# ProDoc_hub_SL2_1A.net
KiCad netlist of a schematic drawn in EasyEDA Pro
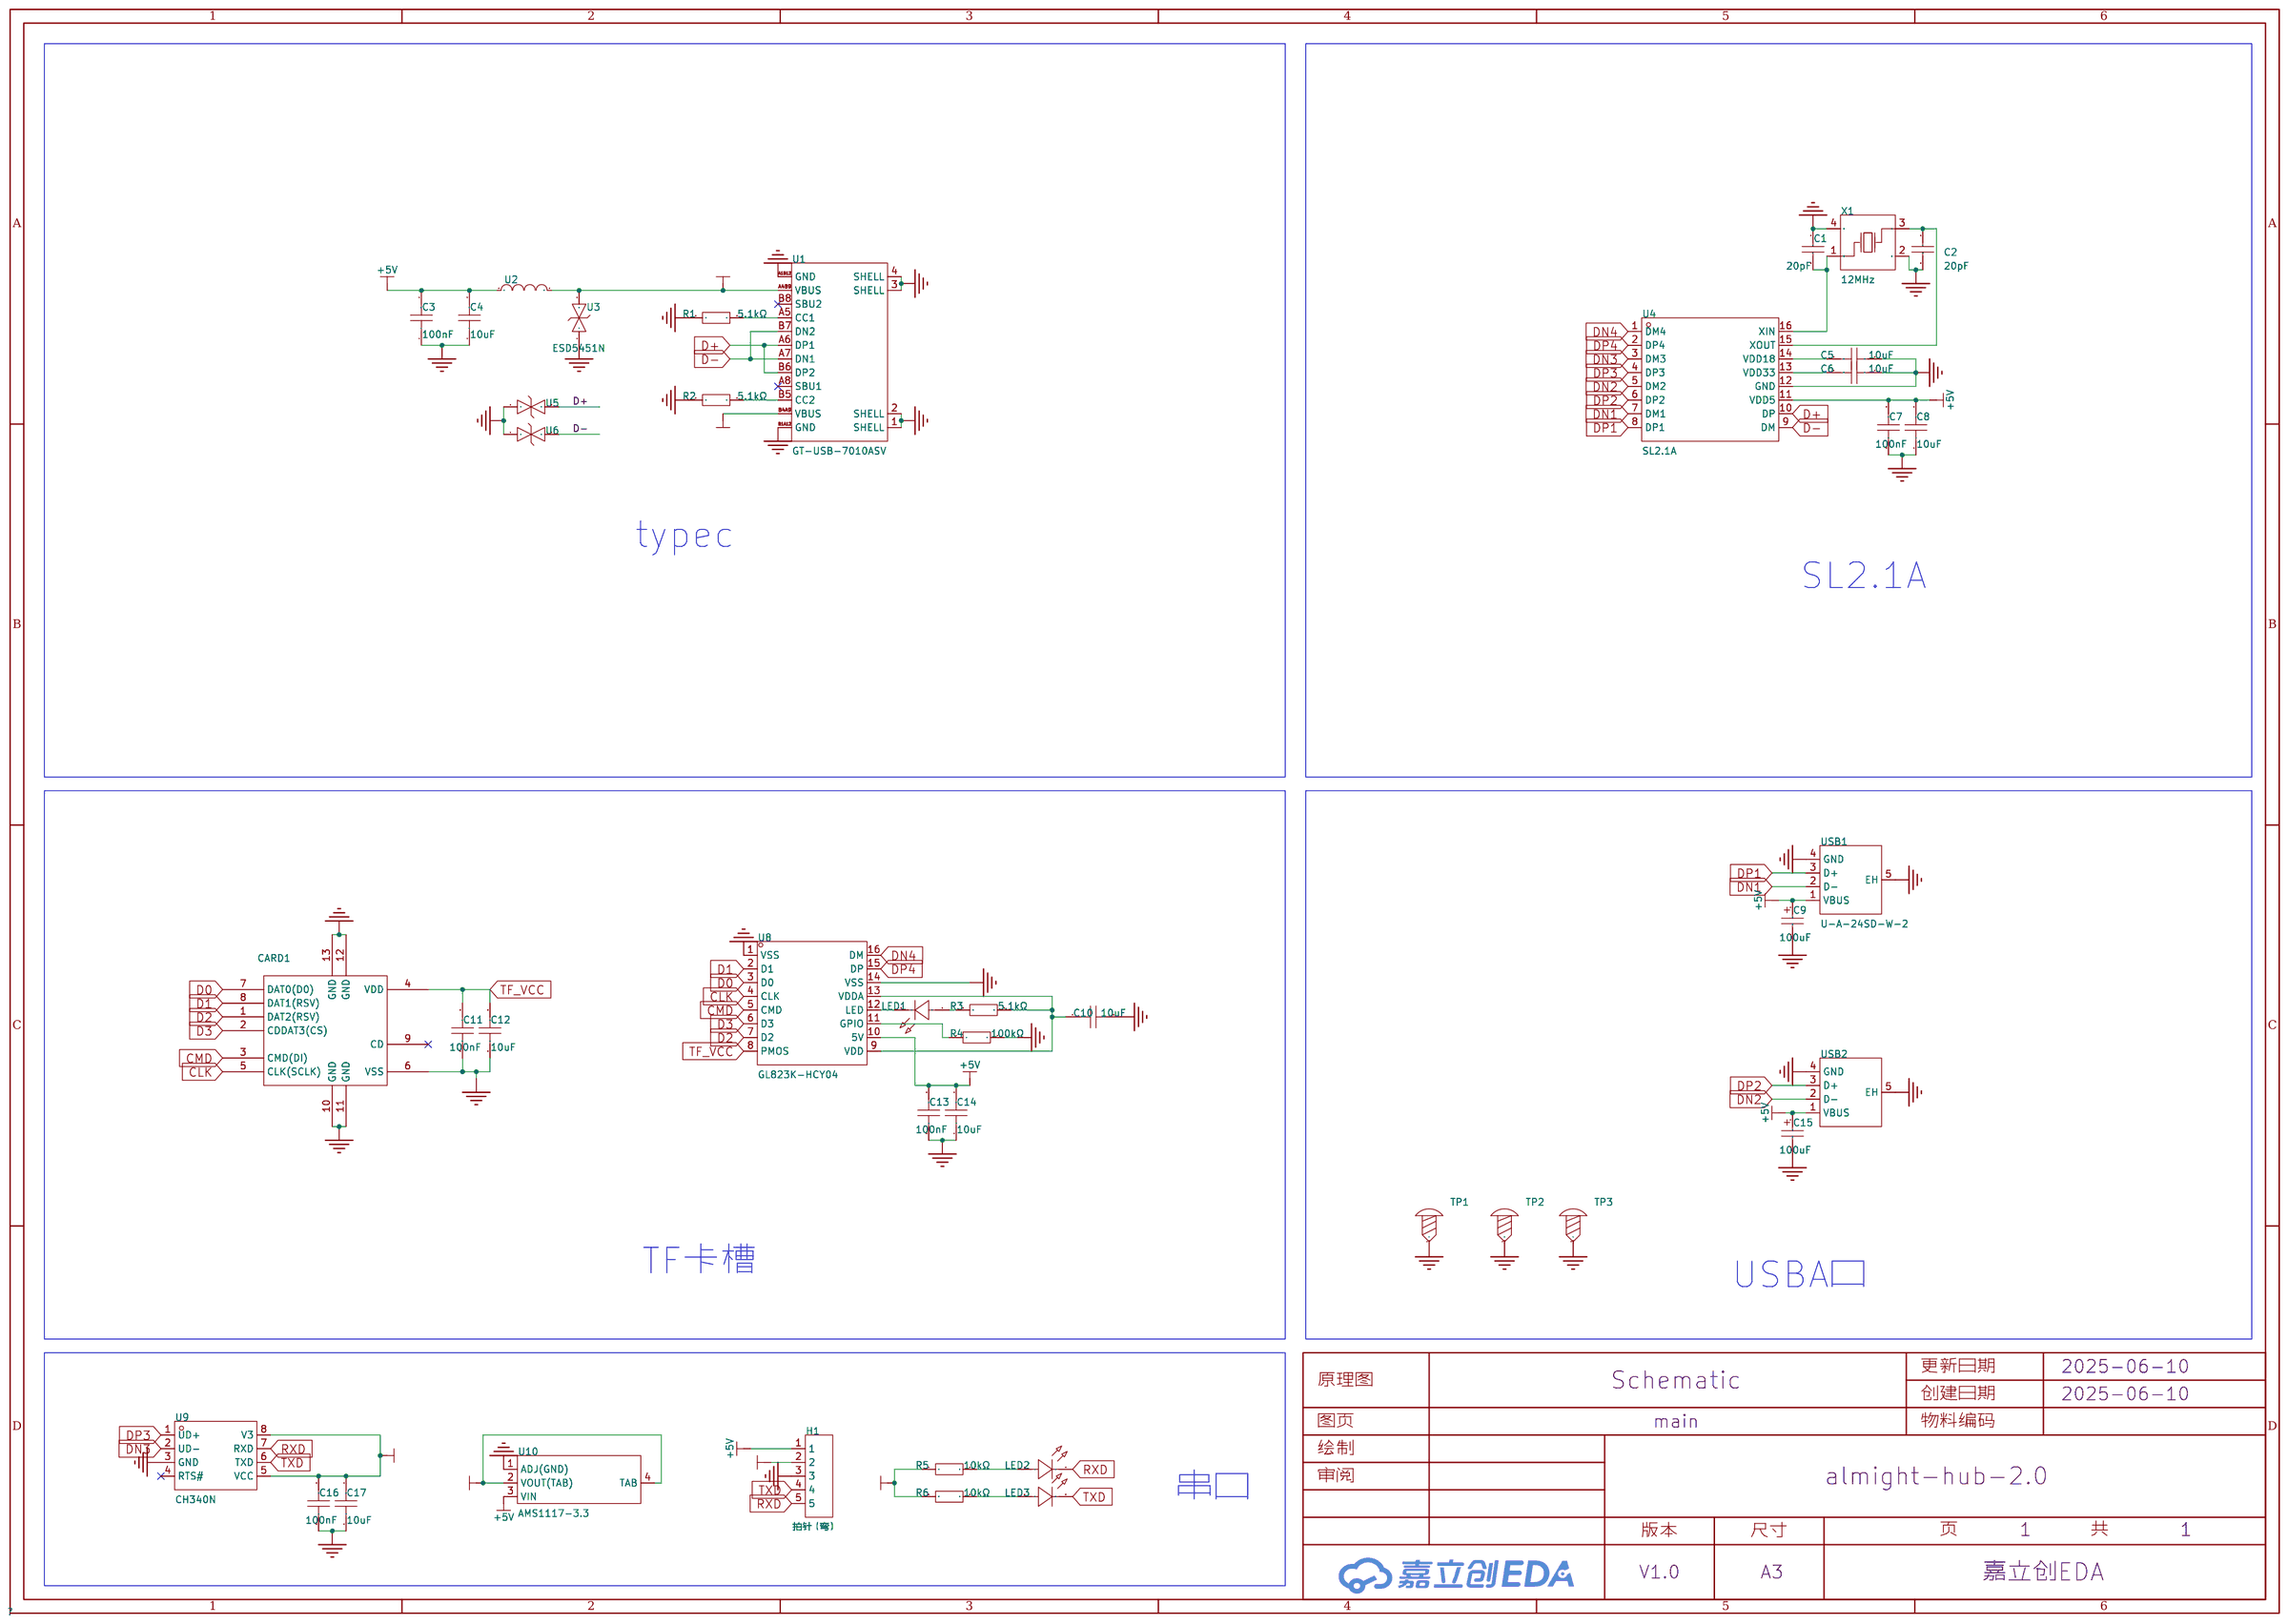
[diagram p0: schematic sheet]

(export (version "E")
  (design (tool "Eeschema 10.0.6"))
  (components
    (comp (ref "C1")
      (value "20pF")
      (footprint "easyedapro:C0402")
      (description "容值:20pF;精度:±5%;额定电压:50V;材质(温度系数):C0G;")
      (fields (field (name "Manufacturer Part") "0402CG200J500NT") (field (name "Manufacturer") "FH(风华)"))
      (libsource (lib "easyedapro") (part "0402CG200J500NT"))
    )
    (comp (ref "C2")
      (value "20pF")
      (footprint "easyedapro:C0402")
      (description "容值:20pF;精度:±5%;额定电压:50V;材质(温度系数):C0G;")
      (fields (field (name "Manufacturer Part") "0402CG200J500NT") (field (name "Manufacturer") "FH(风华)"))
      (libsource (lib "easyedapro") (part "0402CG200J500NT"))
    )
    (comp (ref "C3")
      (value "100nF")
      (footprint "easyedapro:C0402")
      (description "容值:10uF;精度:±20%;额定电压:10V;材质(温度系数):X5R;")
      (fields
        (field (name "Manufacturer Part") "HGC0402R5106M100NTEJ")
        (field (name "Manufacturer") "Chinocera(华瓷)")
      )
      (libsource (lib "easyedapro") (part "HGC0402R5106M100NTEJ"))
    )
    (comp (ref "C4")
      (value "10uF")
      (footprint "easyedapro:C0402")
      (description "容值:10uF;精度:±20%;额定电压:10V;材质(温度系数):X5R;")
      (fields
        (field (name "Manufacturer Part") "HGC0402R5106M100NTEJ")
        (field (name "Manufacturer") "Chinocera(华瓷)")
      )
      (libsource (lib "easyedapro") (part "HGC0402R5106M100NTEJ"))
    )
    (comp (ref "C5")
      (value "10uF")
      (footprint "easyedapro:C0402")
      (description "容值:10uF;精度:±20%;额定电压:10V;材质(温度系数):X5R;")
      (fields
        (field (name "Manufacturer Part") "HGC0402R5106M100NTEJ")
        (field (name "Manufacturer") "Chinocera(华瓷)")
      )
      (libsource (lib "easyedapro") (part "HGC0402R5106M100NTEJ"))
    )
    (comp (ref "C6")
      (value "10uF")
      (footprint "easyedapro:C0402")
      (description "容值:10uF;精度:±20%;额定电压:10V;材质(温度系数):X5R;")
      (fields
        (field (name "Manufacturer Part") "HGC0402R5106M100NTEJ")
        (field (name "Manufacturer") "Chinocera(华瓷)")
      )
      (libsource (lib "easyedapro") (part "HGC0402R5106M100NTEJ"))
    )
    (comp (ref "C7")
      (value "100nF")
      (footprint "easyedapro:C0402")
      (description "容值:10uF;精度:±20%;额定电压:10V;材质(温度系数):X5R;")
      (fields
        (field (name "Manufacturer Part") "HGC0402R5106M100NTEJ")
        (field (name "Manufacturer") "Chinocera(华瓷)")
      )
      (libsource (lib "easyedapro") (part "HGC0402R5106M100NTEJ"))
    )
    (comp (ref "C8")
      (value "10uF")
      (footprint "easyedapro:C0402")
      (description "容值:10uF;精度:±20%;额定电压:10V;材质(温度系数):X5R;")
      (fields
        (field (name "Manufacturer Part") "HGC0402R5106M100NTEJ")
        (field (name "Manufacturer") "Chinocera(华瓷)")
      )
      (libsource (lib "easyedapro") (part "HGC0402R5106M100NTEJ"))
    )
    (comp (ref "C9")
      (value "100uF")
      (footprint "easyedapro:CASE-B_3528")
      (description "容值:100uF;精度:±10%;额定电压:6.3V;等效串联电阻(ESR):1.7Ω@100kHz;")
      (fields (field (name "Manufacturer Part") "TAJB107K006RNJ") (field (name "Manufacturer") "Kyocera AVX"))
      (libsource (lib "easyedapro") (part "TAJB107K006RNJ"))
    )
    (comp (ref "C10")
      (value "10uF")
      (footprint "easyedapro:C0402")
      (description "容值:10uF;精度:±20%;额定电压:10V;材质(温度系数):X5R;")
      (fields
        (field (name "Manufacturer Part") "HGC0402R5106M100NTEJ")
        (field (name "Manufacturer") "Chinocera(华瓷)")
      )
      (libsource (lib "easyedapro") (part "HGC0402R5106M100NTEJ"))
    )
    (comp (ref "C11")
      (value "100nF")
      (footprint "easyedapro:C0402")
      (description "容值:10uF;精度:±20%;额定电压:10V;材质(温度系数):X5R;")
      (fields
        (field (name "Manufacturer Part") "HGC0402R5106M100NTEJ")
        (field (name "Manufacturer") "Chinocera(华瓷)")
      )
      (libsource (lib "easyedapro") (part "HGC0402R5106M100NTEJ"))
    )
    (comp (ref "C12")
      (value "10uF")
      (footprint "easyedapro:C0402")
      (description "容值:10uF;精度:±20%;额定电压:10V;材质(温度系数):X5R;")
      (fields
        (field (name "Manufacturer Part") "HGC0402R5106M100NTEJ")
        (field (name "Manufacturer") "Chinocera(华瓷)")
      )
      (libsource (lib "easyedapro") (part "HGC0402R5106M100NTEJ"))
    )
    (comp (ref "C13")
      (value "100nF")
      (footprint "easyedapro:C0402")
      (description "容值:10uF;精度:±20%;额定电压:10V;材质(温度系数):X5R;")
      (fields
        (field (name "Manufacturer Part") "HGC0402R5106M100NTEJ")
        (field (name "Manufacturer") "Chinocera(华瓷)")
      )
      (libsource (lib "easyedapro") (part "HGC0402R5106M100NTEJ"))
    )
    (comp (ref "C14")
      (value "10uF")
      (footprint "easyedapro:C0402")
      (description "容值:10uF;精度:±20%;额定电压:10V;材质(温度系数):X5R;")
      (fields
        (field (name "Manufacturer Part") "HGC0402R5106M100NTEJ")
        (field (name "Manufacturer") "Chinocera(华瓷)")
      )
      (libsource (lib "easyedapro") (part "HGC0402R5106M100NTEJ"))
    )
    (comp (ref "C15")
      (value "100uF")
      (footprint "easyedapro:CASE-B_3528")
      (description "容值:100uF;精度:±10%;额定电压:6.3V;等效串联电阻(ESR):1.7Ω@100kHz;")
      (fields (field (name "Manufacturer Part") "TAJB107K006RNJ") (field (name "Manufacturer") "Kyocera AVX"))
      (libsource (lib "easyedapro") (part "TAJB107K006RNJ"))
    )
    (comp (ref "C16")
      (value "100nF")
      (footprint "easyedapro:C0402")
      (description "容值:10uF;精度:±20%;额定电压:10V;材质(温度系数):X5R;")
      (fields
        (field (name "Manufacturer Part") "HGC0402R5106M100NTEJ")
        (field (name "Manufacturer") "Chinocera(华瓷)")
      )
      (libsource (lib "easyedapro") (part "HGC0402R5106M100NTEJ"))
    )
    (comp (ref "C17")
      (value "10uF")
      (footprint "easyedapro:C0402")
      (description "容值:10uF;精度:±20%;额定电压:10V;材质(温度系数):X5R;")
      (fields
        (field (name "Manufacturer Part") "HGC0402R5106M100NTEJ")
        (field (name "Manufacturer") "Chinocera(华瓷)")
      )
      (libsource (lib "easyedapro") (part "HGC0402R5106M100NTEJ"))
    )
    (comp (ref "CARD1")
      (value "TF-01A")
      (footprint "easyedapro:TF-SMD_TF-01A")
      (description "卡连接方式:自弹式;卡类型:MicroSD卡(TF卡);连接器类型:卡座;本体最大高度:1.85mm;工作温度范围:-;")
      (fields (field (name "Manufacturer") "韩国韩荣"))
      (libsource (lib "easyedapro") (part "TF-01A"))
    )
    (comp (ref "H1")
      (value "拍针（弯）")
      (footprint "easyedapro:HDR-TH_5P-P2.54-H-M-W10.4")
      (fields (field (name "Manufacturer") "XFCN(兴飞)"))
      (libsource (lib "easyedapro") (part "PZ254R-11-05P"))
    )
    (comp (ref "LED1")
      (value "A-SP192DGHC-C01-4T")
      (footprint "easyedapro:LED0603-FD")
      (fields (field (name "Manufacturer") "Amicc(欧密格光电)"))
      (libsource (lib "easyedapro") (part "A-SP192DGHC-C01-4T"))
    )
    (comp (ref "LED2")
      (value "A-SP192DGHC-C01-4T")
      (footprint "easyedapro:LED0603-FD")
      (fields (field (name "Manufacturer") "Amicc(欧密格光电)"))
      (libsource (lib "easyedapro") (part "A-SP192DGHC-C01-4T"))
    )
    (comp (ref "LED3")
      (value "A-SP192DGHC-C01-4T")
      (footprint "easyedapro:LED0603-FD")
      (fields (field (name "Manufacturer") "Amicc(欧密格光电)"))
      (libsource (lib "easyedapro") (part "A-SP192DGHC-C01-4T"))
    )
    (comp (ref "R1")
      (value "5.1kΩ")
      (footprint "easyedapro:R0402")
      (description "电阻类型:厚膜电阻;阻值:5.1kΩ;精度:±1%;功率:62.5mW;工作电压:50V;温度系数:±100ppm/°C;")
      (fields (field (name "Manufacturer Part") "RC0402FR-075K1L") (field (name "Manufacturer") "YAGEO(国巨)"))
      (libsource (lib "easyedapro") (part "RC0402FR-075K1L"))
    )
    (comp (ref "R2")
      (value "5.1kΩ")
      (footprint "easyedapro:R0402")
      (description "电阻类型:厚膜电阻;阻值:5.1kΩ;精度:±1%;功率:62.5mW;工作电压:50V;温度系数:±100ppm/°C;")
      (fields (field (name "Manufacturer Part") "RC0402FR-075K1L") (field (name "Manufacturer") "YAGEO(国巨)"))
      (libsource (lib "easyedapro") (part "RC0402FR-075K1L"))
    )
    (comp (ref "R3")
      (value "5.1kΩ")
      (footprint "easyedapro:R0402")
      (description "电阻类型:厚膜电阻;阻值:5.1kΩ;精度:±1%;功率:62.5mW;工作电压:50V;温度系数:±100ppm/°C;")
      (fields (field (name "Manufacturer Part") "RC0402FR-075K1L") (field (name "Manufacturer") "YAGEO(国巨)"))
      (libsource (lib "easyedapro") (part "RC0402FR-075K1L"))
    )
    (comp (ref "R4")
      (value "100kΩ")
      (footprint "easyedapro:R0402")
      (description "电阻类型:厚膜电阻;阻值:5.1kΩ;精度:±1%;功率:62.5mW;工作电压:50V;温度系数:±100ppm/°C;")
      (fields (field (name "Manufacturer Part") "RC0402FR-075K1L") (field (name "Manufacturer") "YAGEO(国巨)"))
      (libsource (lib "easyedapro") (part "RC0402FR-075K1L"))
    )
    (comp (ref "R5")
      (value "10kΩ")
      (footprint "easyedapro:R0402")
      (description "电阻类型:厚膜电阻;阻值:5.1kΩ;精度:±1%;功率:62.5mW;工作电压:50V;温度系数:±100ppm/°C;")
      (fields (field (name "Manufacturer Part") "RC0402FR-075K1L") (field (name "Manufacturer") "YAGEO(国巨)"))
      (libsource (lib "easyedapro") (part "RC0402FR-075K1L"))
    )
    (comp (ref "R6")
      (value "10kΩ")
      (footprint "easyedapro:R0402")
      (description "电阻类型:厚膜电阻;阻值:5.1kΩ;精度:±1%;功率:62.5mW;工作电压:50V;温度系数:±100ppm/°C;")
      (fields (field (name "Manufacturer Part") "RC0402FR-075K1L") (field (name "Manufacturer") "YAGEO(国巨)"))
      (libsource (lib "easyedapro") (part "RC0402FR-075K1L"))
    )
    (comp (ref "TP1") (value "~") (footprint "easyedapro:M1螺丝孔") (libsource (lib "easyedapro") (part "螺丝孔")))
    (comp (ref "TP2") (value "~") (footprint "easyedapro:M1螺丝孔") (libsource (lib "easyedapro") (part "螺丝孔")))
    (comp (ref "TP3") (value "~") (footprint "easyedapro:M1螺丝孔") (libsource (lib "easyedapro") (part "螺丝孔")))
    (comp (ref "U1")
      (value "GT-USB-7010ASV")
      (footprint "easyedapro:USB-C-SMD_G-SWITCH_GT-USB-7010ASV")
      (description "连接器类型:Type-C;标准:USB 2.0;公母:母;安装方式:卧贴;触点数量:16P;端口数量:1;额定电流 - 电源:3A;工作温度范围:-40°C~+85°C;")
      (fields (field (name "Manufacturer") "G-Switch(品赞)"))
      (libsource (lib "easyedapro") (part "GT-USB-7010ASV"))
    )
    (comp (ref "U2")
      (value "UPZ1608U221-2R2TF")
      (footprint "easyedapro:L0603")
      (description "标称阻抗@测试频率:220Ω@100MHz;误差:±25%;直流电阻(RDC):50mΩ;")
      (fields (field (name "Manufacturer") "Sunlord(顺络)"))
      (libsource (lib "easyedapro") (part "UPZ1608U221-2R2TF"))
    )
    (comp (ref "U3")
      (value "ESD5451N")
      (footprint "easyedapro:DFN1006-2L-BI")
      (description "极性:双向;反向截止电压(Vrwm):5V;最大钳位电压:9.8V;峰值脉冲电流(Ipp):9A;击穿电压:8V;")
      (fields (field (name "Manufacturer") "HXY MOSFET(华轩阳电子)"))
      (libsource (lib "easyedapro") (part "ESD5451N_C5261080"))
    )
    (comp (ref "U4")
      (value "SL2.1A")
      (footprint "easyedapro:SOP-16_L10.0-W3.9-P1.27-LS6.0-BL")
      (description "SL2.1A是一颗高集成度,高性能,低功耗的USB2.0集线器主控芯片，支持USB2.0高速(480MHz),全速(12MHz)和低速模式(1.5MHz)，内置12MHz晶体振荡器。")
      (fields (field (name "Manufacturer") "CoreChips(和芯润德)"))
      (libsource (lib "easyedapro") (part "SL2.1A"))
    )
    (comp (ref "U5")
      (value "ESD5451N")
      (footprint "easyedapro:DFN1006-2L-BI")
      (description "极性:双向;反向截止电压(Vrwm):5V;最大钳位电压:9.8V;峰值脉冲电流(Ipp):9A;击穿电压:8V;")
      (fields (field (name "Manufacturer") "HXY MOSFET(华轩阳电子)"))
      (libsource (lib "easyedapro") (part "ESD5451N_C5261080"))
    )
    (comp (ref "U6")
      (value "ESD5451N")
      (footprint "easyedapro:DFN1006-2L-BI")
      (description "极性:双向;反向截止电压(Vrwm):5V;最大钳位电压:9.8V;峰值脉冲电流(Ipp):9A;击穿电压:8V;")
      (fields (field (name "Manufacturer") "HXY MOSFET(华轩阳电子)"))
      (libsource (lib "easyedapro") (part "ESD5451N_C5261080"))
    )
    (comp (ref "U8")
      (value "GL823K-HCY04")
      (footprint "easyedapro:SSOP-16_L4.9-W3.9-P0.64-LS6.0-BL")
      (description "应用功能:-;接口协议:-;")
      (fields (field (name "Manufacturer") "GENESYS(创惟)"))
      (libsource (lib "easyedapro") (part "GL823K-HCY04"))
    )
    (comp (ref "U9")
      (value "CH340N")
      (footprint "easyedapro:SOP-8_L5.0-W4.0-P1.27-LS6.0-BL")
      (description "应用功能:USB转串口;接口协议:USB 2.0;通道数:-;数据速率:2Mbps;")
      (fields (field (name "Manufacturer") "WCH(南京沁恒)"))
      (libsource (lib "easyedapro") (part "CH340N"))
    )
    (comp (ref "U10")
      (value "AMS1117-3.3")
      (footprint "easyedapro:SOT-223-4_L6.5-W3.5-P2.30-LS7.0-BR")
      (description "输出类型:固定;工作电压:12V;输出电压:3.3V;输出电流:1A;电源纹波抑制比(PSRR):60dB@(120Hz);输出极性:正极;")
      (fields (field (name "Manufacturer") "UMW(友台半导体)"))
      (libsource (lib "easyedapro") (part "AMS1117-3.3_C347222"))
    )
    (comp (ref "USB1")
      (value "U-A-24SD-W-2")
      (footprint "easyedapro:USB-A-SMD_U-A-24SD-W-2")
      (description "连接器类型:Type-A;标准:USB 2.0;公母:母;端口数量:1;触点数量:4P;安装方式:沉板;额定电流 - 电源:1.5A;工作温度范围:-;")
      (fields (field (name "Manufacturer") "韩国韩荣"))
      (libsource (lib "easyedapro") (part "U-A-24SD-W-2"))
    )
    (comp (ref "USB2")
      (value "U-A-24SD-W-2")
      (footprint "easyedapro:USB-A-SMD_U-A-24SD-W-2")
      (description "连接器类型:Type-A;标准:USB 2.0;公母:母;端口数量:1;触点数量:4P;安装方式:沉板;额定电流 - 电源:1.5A;工作温度范围:-;")
      (fields (field (name "Manufacturer") "韩国韩荣"))
      (libsource (lib "easyedapro") (part "U-A-24SD-W-2"))
    )
    (comp (ref "X1")
      (value "12MHz")
      (footprint "easyedapro:CRYSTAL-SMD_4P-L3.2-W2.5-BL")
      (description "晶振类型:贴片晶振;频率:12MHz;常温频差:±10ppm;外接负载电容:20pF;频率稳定度(全温):±20ppm;")
      (fields (field (name "Manufacturer Part") "X322512MSB4SI") (field (name "Manufacturer") "YXC(扬兴晶振)"))
      (libsource (lib "easyedapro") (part "X322512MSB4SI"))
    )
  )
  (nets
    (net (code "1") (name "+5V") (class "Default")
      (node (ref "C13") (pin "2") (pinfunction "2_2") (pintype "unspecified"))
      (node (ref "C14") (pin "2") (pinfunction "2_2") (pintype "unspecified"))
      (node (ref "C15") (pin "1") (pinfunction "1_1") (pintype "input"))
      (node (ref "C3") (pin "2") (pinfunction "2_2") (pintype "unspecified"))
      (node (ref "C4") (pin "2") (pinfunction "2_2") (pintype "unspecified"))
      (node (ref "C7") (pin "2") (pinfunction "2_2") (pintype "unspecified"))
      (node (ref "C8") (pin "2") (pinfunction "2_2") (pintype "unspecified"))
      (node (ref "C9") (pin "1") (pinfunction "1_1") (pintype "input"))
      (node (ref "H1") (pin "1") (pinfunction "1_1") (pintype "unspecified"))
      (node (ref "U10") (pin "3") (pinfunction "VIN_3") (pintype "unspecified"))
      (node (ref "U2") (pin "1") (pinfunction "1_1") (pintype "unspecified"))
      (node (ref "U4") (pin "11") (pinfunction "VDD5_11") (pintype "unspecified"))
      (node (ref "U8") (pin "10") (pinfunction "5V_10") (pintype "unspecified"))
      (node (ref "USB1") (pin "1") (pinfunction "VBUS_1") (pintype "unspecified"))
      (node (ref "USB2") (pin "1") (pinfunction "VBUS_1") (pintype "unspecified"))
    )
    (net (code "2") (name "3V3") (class "Default")
      (node (ref "C16") (pin "2") (pinfunction "2_2") (pintype "unspecified"))
      (node (ref "C17") (pin "2") (pinfunction "2_2") (pintype "unspecified"))
      (node (ref "H1") (pin "2") (pinfunction "2_2") (pintype "unspecified"))
      (node (ref "R5") (pin "1") (pinfunction "1_1") (pintype "input"))
      (node (ref "R6") (pin "1") (pinfunction "1_1") (pintype "input"))
      (node (ref "U10") (pin "2") (pinfunction "VOUT(TAB)_2") (pintype "unspecified"))
      (node (ref "U10") (pin "4") (pinfunction "TAB_4") (pintype "unspecified"))
      (node (ref "U9") (pin "5") (pinfunction "VCC_5") (pintype "unspecified"))
      (node (ref "U9") (pin "8") (pinfunction "V3_8") (pintype "unspecified"))
    )
    (net (code "3") (name "CLK") (class "Default")
      (node (ref "CARD1") (pin "5") (pinfunction "CLK(SCLK)_5") (pintype "input"))
      (node (ref "U8") (pin "4") (pinfunction "CLK_4") (pintype "unspecified"))
    )
    (net (code "4") (name "CMD") (class "Default")
      (node (ref "CARD1") (pin "3") (pinfunction "CMD(DI)_3") (pintype "input"))
      (node (ref "U8") (pin "5") (pinfunction "CMD_5") (pintype "unspecified"))
    )
    (net (code "5") (name "D+") (class "Default")
      (node (ref "U1") (pin "A6") (pinfunction "DP1_A6") (pintype "unspecified"))
      (node (ref "U1") (pin "B6") (pinfunction "DP2_B6") (pintype "unspecified"))
      (node (ref "U4") (pin "10") (pinfunction "DP_10") (pintype "unspecified"))
      (node (ref "U5") (pin "2") (pinfunction "2_2") (pintype "unspecified"))
    )
    (net (code "6") (name "D-") (class "Default")
      (node (ref "U1") (pin "A7") (pinfunction "DN1_A7") (pintype "unspecified"))
      (node (ref "U1") (pin "B7") (pinfunction "DN2_B7") (pintype "unspecified"))
      (node (ref "U4") (pin "9") (pinfunction "DM_9") (pintype "unspecified"))
      (node (ref "U6") (pin "2") (pinfunction "2_2") (pintype "unspecified"))
    )
    (net (code "7") (name "D0") (class "Default")
      (node (ref "CARD1") (pin "7") (pinfunction "DAT0(D0)_7") (pintype "bidirectional"))
      (node (ref "U8") (pin "3") (pinfunction "D0_3") (pintype "unspecified"))
    )
    (net (code "8") (name "D1") (class "Default")
      (node (ref "CARD1") (pin "8") (pinfunction "DAT1(RSV)_8") (pintype "bidirectional"))
      (node (ref "U8") (pin "2") (pinfunction "D1_2") (pintype "unspecified"))
    )
    (net (code "9") (name "D2") (class "Default")
      (node (ref "CARD1") (pin "1") (pinfunction "DAT2(RSV)_1") (pintype "bidirectional"))
      (node (ref "U8") (pin "7") (pinfunction "D2_7") (pintype "unspecified"))
    )
    (net (code "10") (name "D3") (class "Default")
      (node (ref "CARD1") (pin "2") (pinfunction "CDDAT3(CS)_2") (pintype "bidirectional"))
      (node (ref "U8") (pin "6") (pinfunction "D3_6") (pintype "unspecified"))
    )
    (net (code "11") (name "DN1") (class "Default")
      (node (ref "U4") (pin "7") (pinfunction "DM1_7") (pintype "unspecified"))
      (node (ref "USB1") (pin "2") (pinfunction "D-_2") (pintype "unspecified"))
    )
    (net (code "12") (name "DN2") (class "Default")
      (node (ref "U4") (pin "5") (pinfunction "DM2_5") (pintype "unspecified"))
      (node (ref "USB2") (pin "2") (pinfunction "D-_2") (pintype "unspecified"))
    )
    (net (code "13") (name "DN3") (class "Default")
      (node (ref "U4") (pin "3") (pinfunction "DM3_3") (pintype "unspecified"))
      (node (ref "U9") (pin "2") (pinfunction "UD-_2") (pintype "unspecified"))
    )
    (net (code "14") (name "DN4") (class "Default")
      (node (ref "U4") (pin "1") (pinfunction "DM4_1") (pintype "unspecified"))
      (node (ref "U8") (pin "16") (pinfunction "DM_16") (pintype "unspecified"))
    )
    (net (code "15") (name "DP1") (class "Default")
      (node (ref "U4") (pin "8") (pinfunction "DP1_8") (pintype "unspecified"))
      (node (ref "USB1") (pin "3") (pinfunction "D+_3") (pintype "unspecified"))
    )
    (net (code "16") (name "DP2") (class "Default")
      (node (ref "U4") (pin "6") (pinfunction "DP2_6") (pintype "unspecified"))
      (node (ref "USB2") (pin "3") (pinfunction "D+_3") (pintype "unspecified"))
    )
    (net (code "17") (name "DP3") (class "Default")
      (node (ref "U4") (pin "4") (pinfunction "DP3_4") (pintype "unspecified"))
      (node (ref "U9") (pin "1") (pinfunction "UD+_1") (pintype "unspecified"))
    )
    (net (code "18") (name "DP4") (class "Default")
      (node (ref "U4") (pin "2") (pinfunction "DP4_2") (pintype "unspecified"))
      (node (ref "U8") (pin "15") (pinfunction "DP_15") (pintype "unspecified"))
    )
    (net (code "19") (name "GND") (class "Default")
      (node (ref "C1") (pin "1") (pinfunction "1_1") (pintype "input"))
      (node (ref "C10") (pin "2") (pinfunction "2_2") (pintype "unspecified"))
      (node (ref "C11") (pin "1") (pinfunction "1_1") (pintype "unspecified"))
      (node (ref "C12") (pin "1") (pinfunction "1_1") (pintype "unspecified"))
      (node (ref "C13") (pin "1") (pinfunction "1_1") (pintype "unspecified"))
      (node (ref "C14") (pin "1") (pinfunction "1_1") (pintype "unspecified"))
      (node (ref "C15") (pin "2") (pinfunction "2_2") (pintype "input"))
      (node (ref "C16") (pin "1") (pinfunction "1_1") (pintype "unspecified"))
      (node (ref "C17") (pin "1") (pinfunction "1_1") (pintype "unspecified"))
      (node (ref "C2") (pin "2") (pinfunction "2_2") (pintype "input"))
      (node (ref "C3") (pin "1") (pinfunction "1_1") (pintype "unspecified"))
      (node (ref "C4") (pin "1") (pinfunction "1_1") (pintype "unspecified"))
      (node (ref "C5") (pin "1") (pinfunction "1_1") (pintype "unspecified"))
      (node (ref "C6") (pin "1") (pinfunction "1_1") (pintype "unspecified"))
      (node (ref "C7") (pin "1") (pinfunction "1_1") (pintype "unspecified"))
      (node (ref "C8") (pin "1") (pinfunction "1_1") (pintype "unspecified"))
      (node (ref "C9") (pin "2") (pinfunction "2_2") (pintype "input"))
      (node (ref "CARD1") (pin "10") (pinfunction "GND_10") (pintype "input"))
      (node (ref "CARD1") (pin "11") (pinfunction "GND_11") (pintype "input"))
      (node (ref "CARD1") (pin "12") (pinfunction "GND_12") (pintype "input"))
      (node (ref "CARD1") (pin "13") (pinfunction "GND_13") (pintype "input"))
      (node (ref "CARD1") (pin "6") (pinfunction "VSS_6") (pintype "input"))
      (node (ref "H1") (pin "3") (pinfunction "3_3") (pintype "unspecified"))
      (node (ref "R1") (pin "1") (pinfunction "1_1") (pintype "input"))
      (node (ref "R2") (pin "1") (pinfunction "1_1") (pintype "input"))
      (node (ref "R4") (pin "2") (pinfunction "2_2") (pintype "input"))
      (node (ref "TP1") (pin "1") (pinfunction "1_1") (pintype "input"))
      (node (ref "TP2") (pin "1") (pinfunction "1_1") (pintype "input"))
      (node (ref "TP3") (pin "1") (pinfunction "1_1") (pintype "input"))
      (node (ref "U1") (pin "1") (pinfunction "SHELL_1") (pintype "unspecified"))
      (node (ref "U1") (pin "2") (pinfunction "SHELL_2") (pintype "unspecified"))
      (node (ref "U1") (pin "3") (pinfunction "SHELL_3") (pintype "unspecified"))
      (node (ref "U1") (pin "4") (pinfunction "SHELL_4") (pintype "unspecified"))
      (node (ref "U1") (pin "A1B12") (pinfunction "GND_A1B12") (pintype "unspecified"))
      (node (ref "U1") (pin "B1A12") (pinfunction "GND_B1A12") (pintype "unspecified"))
      (node (ref "U10") (pin "1") (pinfunction "ADJ(GND)_1") (pintype "unspecified"))
      (node (ref "U3") (pin "1") (pinfunction "1_1") (pintype "unspecified"))
      (node (ref "U4") (pin "12") (pinfunction "GND_12") (pintype "unspecified"))
      (node (ref "U5") (pin "1") (pinfunction "1_1") (pintype "unspecified"))
      (node (ref "U6") (pin "1") (pinfunction "1_1") (pintype "unspecified"))
      (node (ref "U8") (pin "1") (pinfunction "VSS_1") (pintype "unspecified"))
      (node (ref "U8") (pin "14") (pinfunction "VSS_14") (pintype "unspecified"))
      (node (ref "U9") (pin "3") (pinfunction "GND_3") (pintype "unspecified"))
      (node (ref "USB1") (pin "4") (pinfunction "GND_4") (pintype "unspecified"))
      (node (ref "USB1") (pin "5") (pinfunction "EH_5") (pintype "unspecified"))
      (node (ref "USB2") (pin "4") (pinfunction "GND_4") (pintype "unspecified"))
      (node (ref "USB2") (pin "5") (pinfunction "EH_5") (pintype "unspecified"))
      (node (ref "X1") (pin "2") (pinfunction "GND_2") (pintype "unspecified"))
      (node (ref "X1") (pin "4") (pinfunction "GND_4") (pintype "unspecified"))
    )
    (net (code "20") (name "Net-(LED1-A)") (class "Default")
      (node (ref "LED1") (pin "1") (pinfunction "A_1") (pintype "unspecified"))
      (node (ref "R3") (pin "1") (pinfunction "1_1") (pintype "input"))
    )
    (net (code "21") (name "Net-(LED1-K)") (class "Default")
      (node (ref "LED1") (pin "2") (pinfunction "K_2") (pintype "unspecified"))
      (node (ref "U8") (pin "12") (pinfunction "LED_12") (pintype "unspecified"))
    )
    (net (code "22") (name "Net-(LED2-A)") (class "Default")
      (node (ref "LED2") (pin "1") (pinfunction "A_1") (pintype "unspecified"))
      (node (ref "R5") (pin "2") (pinfunction "2_2") (pintype "input"))
    )
    (net (code "23") (name "Net-(LED3-A)") (class "Default")
      (node (ref "LED3") (pin "1") (pinfunction "A_1") (pintype "unspecified"))
      (node (ref "R6") (pin "2") (pinfunction "2_2") (pintype "input"))
    )
    (net (code "24") (name "Net-(U1-CC1)") (class "Default")
      (node (ref "R1") (pin "2") (pinfunction "2_2") (pintype "input"))
      (node (ref "U1") (pin "A5") (pinfunction "CC1_A5") (pintype "unspecified"))
    )
    (net (code "25") (name "Net-(U1-CC2)") (class "Default")
      (node (ref "R2") (pin "2") (pinfunction "2_2") (pintype "input"))
      (node (ref "U1") (pin "B5") (pinfunction "CC2_B5") (pintype "unspecified"))
    )
    (net (code "26") (name "Net-(U4-VDD18)") (class "Default")
      (node (ref "C5") (pin "2") (pinfunction "2_2") (pintype "unspecified"))
      (node (ref "U4") (pin "14") (pinfunction "VDD18_14") (pintype "unspecified"))
    )
    (net (code "27") (name "Net-(U4-VDD33)") (class "Default")
      (node (ref "C6") (pin "2") (pinfunction "2_2") (pintype "unspecified"))
      (node (ref "U4") (pin "13") (pinfunction "VDD33_13") (pintype "unspecified"))
    )
    (net (code "28") (name "Net-(U4-XIN)") (class "Default")
      (node (ref "C1") (pin "2") (pinfunction "2_2") (pintype "input"))
      (node (ref "U4") (pin "16") (pinfunction "XIN_16") (pintype "unspecified"))
      (node (ref "X1") (pin "1") (pinfunction "OSC1_1") (pintype "unspecified"))
    )
    (net (code "29") (name "Net-(U4-XOUT)") (class "Default")
      (node (ref "C2") (pin "1") (pinfunction "1_1") (pintype "input"))
      (node (ref "U4") (pin "15") (pinfunction "XOUT_15") (pintype "unspecified"))
      (node (ref "X1") (pin "3") (pinfunction "OSC2_3") (pintype "unspecified"))
    )
    (net (code "30") (name "Net-(U8-GPIO)") (class "Default")
      (node (ref "R4") (pin "1") (pinfunction "1_1") (pintype "input"))
      (node (ref "U8") (pin "11") (pinfunction "GPIO_11") (pintype "unspecified"))
    )
    (net (code "31") (name "Net-(U8-VDD)") (class "Default")
      (node (ref "C10") (pin "1") (pinfunction "1_1") (pintype "unspecified"))
      (node (ref "R3") (pin "2") (pinfunction "2_2") (pintype "input"))
      (node (ref "U8") (pin "13") (pinfunction "VDDA_13") (pintype "unspecified"))
      (node (ref "U8") (pin "9") (pinfunction "VDD_9") (pintype "unspecified"))
    )
    (net (code "32") (name "RXD") (class "Default")
      (node (ref "H1") (pin "5") (pinfunction "5_5") (pintype "unspecified"))
      (node (ref "LED2") (pin "2") (pinfunction "K_2") (pintype "unspecified"))
      (node (ref "U9") (pin "7") (pinfunction "RXD_7") (pintype "unspecified"))
    )
    (net (code "33") (name "TF_VCC") (class "Default")
      (node (ref "C11") (pin "2") (pinfunction "2_2") (pintype "unspecified"))
      (node (ref "C12") (pin "2") (pinfunction "2_2") (pintype "unspecified"))
      (node (ref "CARD1") (pin "4") (pinfunction "VDD_4") (pintype "input"))
      (node (ref "U8") (pin "8") (pinfunction "PMOS_8") (pintype "unspecified"))
    )
    (net (code "34") (name "TXD") (class "Default")
      (node (ref "H1") (pin "4") (pinfunction "4_4") (pintype "unspecified"))
      (node (ref "LED3") (pin "2") (pinfunction "K_2") (pintype "unspecified"))
      (node (ref "U9") (pin "6") (pinfunction "TXD_6") (pintype "unspecified"))
    )
    (net (code "35") (name "VBUS") (class "Default")
      (node (ref "U1") (pin "A4B9") (pinfunction "VBUS_A4B9") (pintype "unspecified"))
      (node (ref "U1") (pin "B4A9") (pinfunction "VBUS_B4A9") (pintype "unspecified"))
      (node (ref "U2") (pin "2") (pinfunction "2_2") (pintype "unspecified"))
      (node (ref "U3") (pin "2") (pinfunction "2_2") (pintype "unspecified"))
    )
    (net (code "36") (name "unconnected-(CARD1-CD-Pad9)") (class "Default")
      (node (ref "CARD1") (pin "9") (pinfunction "CD_9") (pintype "input+no_connect"))
    )
    (net (code "37") (name "unconnected-(U1-SBU1-PadA8)") (class "Default")
      (node (ref "U1") (pin "A8") (pinfunction "SBU1_A8") (pintype "unspecified+no_connect"))
    )
    (net (code "38") (name "unconnected-(U1-SBU2-PadB8)") (class "Default")
      (node (ref "U1") (pin "B8") (pinfunction "SBU2_B8") (pintype "unspecified+no_connect"))
    )
    (net (code "39") (name "unconnected-(U9-RTS#-Pad4)") (class "Default")
      (node (ref "U9") (pin "4") (pinfunction "RTS#_4") (pintype "unspecified+no_connect"))
    )
  )
)
